# DA14580_QFN40_0v5_P.net
KiCad netlist of a schematic drawn in EAGLE
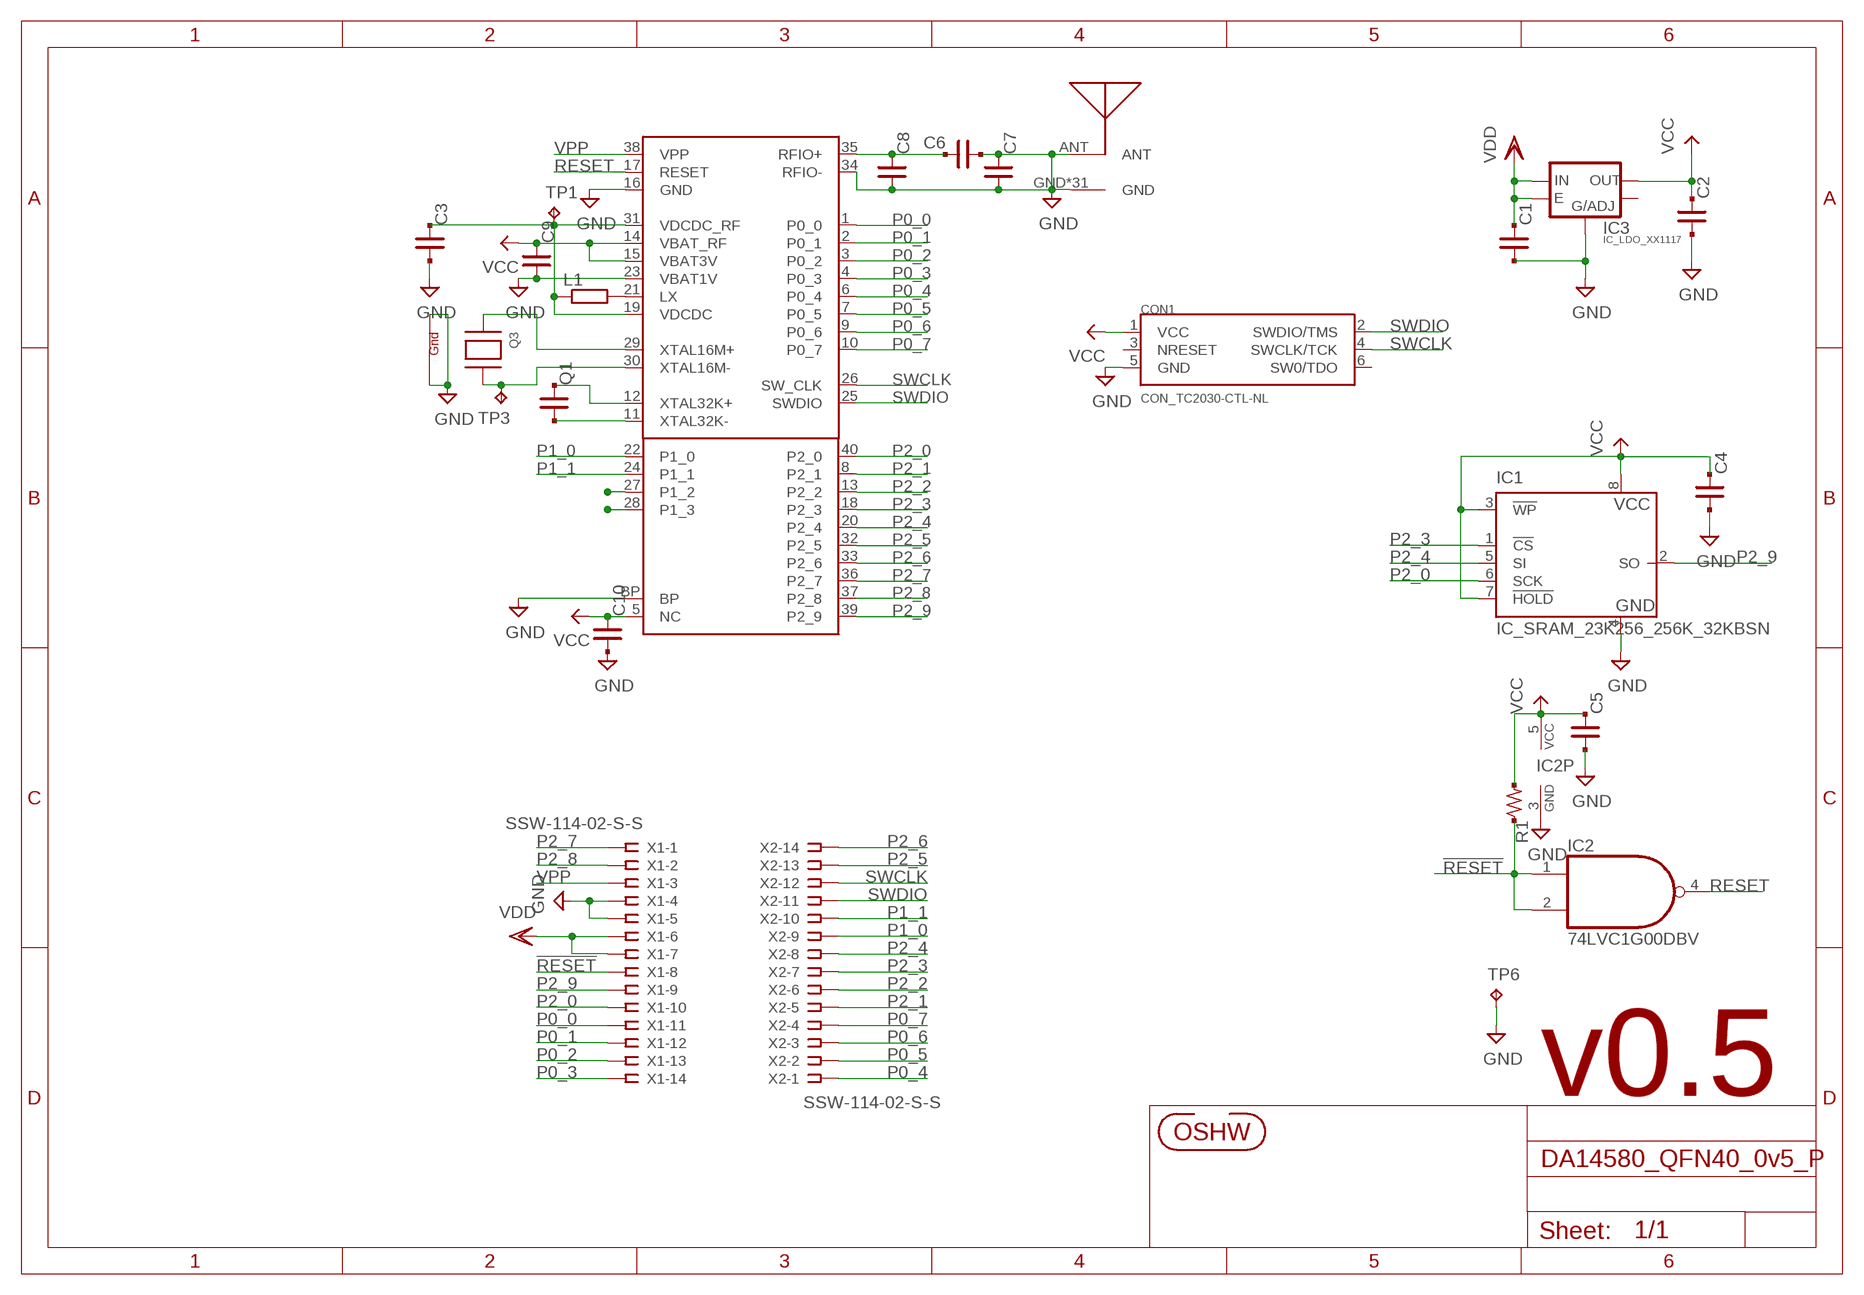
[diagram p0: schematic, sheet 1]

(export (version "E")
  (design (tool "Eeschema 10.0.6"))
  (components
    (comp (ref "C1")
      (value "C_PAD_PAD_1005")
      (footprint "eagle-import:C0402")
      (libsource (lib "eagle-import") (part "C_PAD_PAD_1005"))
    )
    (comp (ref "C2")
      (value "C_PAD_PAD_1005")
      (footprint "eagle-import:C0402")
      (libsource (lib "eagle-import") (part "C_PAD_PAD_1005"))
    )
    (comp (ref "C3")
      (value "C_PAD_PAD_1005")
      (footprint "eagle-import:C0402")
      (libsource (lib "eagle-import") (part "C_PAD_PAD_1005"))
    )
    (comp (ref "C4")
      (value "C_PAD_PAD_1005")
      (footprint "eagle-import:C0402")
      (libsource (lib "eagle-import") (part "C_PAD_PAD_1005"))
    )
    (comp (ref "C5")
      (value "C_PAD_PAD_1005")
      (footprint "eagle-import:C0402")
      (libsource (lib "eagle-import") (part "C_PAD_PAD_1005"))
    )
    (comp (ref "C6")
      (value "C_PAD_PAD_1005")
      (footprint "eagle-import:C0402")
      (libsource (lib "eagle-import") (part "C_PAD_PAD_1005"))
    )
    (comp (ref "C7")
      (value "C_PAD_PAD_1005")
      (footprint "eagle-import:C0402")
      (libsource (lib "eagle-import") (part "C_PAD_PAD_1005"))
    )
    (comp (ref "C8")
      (value "C_PAD_PAD_1005")
      (footprint "eagle-import:C0402")
      (libsource (lib "eagle-import") (part "C_PAD_PAD_1005"))
    )
    (comp (ref "C9")
      (value "C_PAD_PAD_1005")
      (footprint "eagle-import:C0402")
      (libsource (lib "eagle-import") (part "C_PAD_PAD_1005"))
    )
    (comp (ref "C10")
      (value "C_PAD_PAD_1005")
      (footprint "eagle-import:C0402")
      (libsource (lib "eagle-import") (part "C_PAD_PAD_1005"))
    )
    (comp (ref "CON1")
      (value "CON_TC2030-CTL-NL")
      (footprint "eagle-import:CON_TC2030-IDC-NL")
      (libsource (lib "eagle-import") (part "CON_TC2030-CTL-NL"))
    )
    (comp (ref "IC1")
      (value "IC_SRAM_23K256_256K_32KBSN")
      (footprint "eagle-import:IC_08_1.27_150MIL")
      (libsource (lib "eagle-import") (part "IC_SRAM_23K256_256K_32KBSN"))
    )
    (comp (ref "IC2")
      (value "74LVC1G00DBV")
      (footprint "eagle-import:SOT23-5")
      (libsource (lib "eagle-import") (part "741G00DBVLVC"))
    )
    (comp (ref "IC3")
      (value "IC_LDO_XX1117")
      (footprint "eagle-import:IC_05_0.95_50MIL")
      (libsource (lib "eagle-import") (part "IC_LDO_XX1117"))
    )
    (comp (ref "L1")
      (value "R-EU_R0603")
      (footprint "eagle-import:R0603")
      (libsource (lib "eagle-import") (part "R-EU_R0603"))
    )
    (comp (ref "Q1")
      (value "C_PAD_PAD_3216")
      (footprint "eagle-import:CR_3216")
      (libsource (lib "eagle-import") (part "C_PAD_PAD_3216"))
    )
    (comp (ref "Q3")
      (value "XTAL-4-3225")
      (footprint "eagle-import:NX3225")
      (libsource (lib "eagle-import") (part "XTAL-4-3225"))
    )
    (comp (ref "R1")
      (value "R_US_PAD_PAD_1005")
      (footprint "eagle-import:C0402")
      (libsource (lib "eagle-import") (part "R_US_PAD_PAD_1005"))
    )
    (comp (ref "TP1")
      (value "TPTP07R")
      (footprint "eagle-import:TP07R")
      (libsource (lib "eagle-import") (part "TPTP07R"))
    )
    (comp (ref "TP3")
      (value "TPTP07R")
      (footprint "eagle-import:TP07R")
      (libsource (lib "eagle-import") (part "TPTP07R"))
    )
    (comp (ref "TP6")
      (value "TPPAD1-13")
      (footprint "eagle-import:P1-13")
      (libsource (lib "eagle-import") (part "TPPAD1-13"))
    )
    (comp (ref "U$1")
      (value "ANT_IFA")
      (footprint "eagle-import:ANT_IFA_V2")
      (libsource (lib "eagle-import") (part "ANT_IFA"))
    )
    (comp (ref "U$2")
      (value "ICON_OSHW")
      (footprint "eagle-import:ICON_OSHW")
      (libsource (lib "eagle-import") (part "ICON_OSHW"))
    )
    (comp (ref "U1")
      (value "IC_DA14580_QFN40")
      (footprint "eagle-import:QFN40_0.4P5.0X5.0")
      (libsource (lib "eagle-import") (part "IC_DA14580_QFN40"))
    )
    (comp (ref "X1")
      (value "SSW-114-02-S-S")
      (footprint "eagle-import:SSW-114-02-S-S")
      (libsource (lib "eagle-import") (part "SSW-114-02-S-S"))
    )
    (comp (ref "X2")
      (value "SSW-114-02-S-S")
      (footprint "eagle-import:SSW-114-02-S-S")
      (libsource (lib "eagle-import") (part "SSW-114-02-S-S"))
    )
  )
  (nets
    (net (code "1") (name "/P0_0") (class "Default")
      (node (ref "U1") (pin "1") (pinfunction "P0_0_1") (pintype "bidirectional"))
      (node (ref "X1") (pin "11") (pinfunction "1_11") (pintype "passive"))
    )
    (net (code "2") (name "/P0_1") (class "Default")
      (node (ref "U1") (pin "2") (pinfunction "P0_1_2") (pintype "bidirectional"))
      (node (ref "X1") (pin "12") (pinfunction "1_12") (pintype "passive"))
    )
    (net (code "3") (name "/P0_2") (class "Default")
      (node (ref "U1") (pin "3") (pinfunction "P0_2_3") (pintype "bidirectional"))
      (node (ref "X1") (pin "13") (pinfunction "1_13") (pintype "passive"))
    )
    (net (code "4") (name "/P0_3") (class "Default")
      (node (ref "U1") (pin "4") (pinfunction "P0_3_4") (pintype "bidirectional"))
      (node (ref "X1") (pin "14") (pinfunction "1_14") (pintype "passive"))
    )
    (net (code "5") (name "/P0_4") (class "Default")
      (node (ref "U1") (pin "6") (pinfunction "P0_4_6") (pintype "bidirectional"))
      (node (ref "X2") (pin "1") (pinfunction "1_1") (pintype "passive"))
    )
    (net (code "6") (name "/P0_5") (class "Default")
      (node (ref "U1") (pin "7") (pinfunction "P0_5_7") (pintype "bidirectional"))
      (node (ref "X2") (pin "2") (pinfunction "1_2") (pintype "passive"))
    )
    (net (code "7") (name "/P0_6") (class "Default")
      (node (ref "U1") (pin "9") (pinfunction "P0_6_9") (pintype "bidirectional"))
      (node (ref "X2") (pin "3") (pinfunction "1_3") (pintype "passive"))
    )
    (net (code "8") (name "/P0_7") (class "Default")
      (node (ref "U1") (pin "10") (pinfunction "P0_7_10") (pintype "bidirectional"))
      (node (ref "X2") (pin "4") (pinfunction "1_4") (pintype "passive"))
    )
    (net (code "9") (name "/P1_0") (class "Default")
      (node (ref "U1") (pin "22") (pinfunction "P1_0_22") (pintype "bidirectional"))
      (node (ref "X2") (pin "9") (pinfunction "1_9") (pintype "passive"))
    )
    (net (code "10") (name "/P1_1") (class "Default")
      (node (ref "U1") (pin "24") (pinfunction "P1_1_24") (pintype "bidirectional"))
      (node (ref "X2") (pin "10") (pinfunction "1_10") (pintype "passive"))
    )
    (net (code "11") (name "/P2_0") (class "Default")
      (node (ref "IC1") (pin "6") (pinfunction "SCK_6") (pintype "input"))
      (node (ref "U1") (pin "40") (pinfunction "P2_0_40") (pintype "bidirectional"))
      (node (ref "X1") (pin "10") (pinfunction "1_10") (pintype "passive"))
    )
    (net (code "12") (name "/P2_1") (class "Default")
      (node (ref "U1") (pin "8") (pinfunction "P2_1_8") (pintype "bidirectional"))
      (node (ref "X2") (pin "5") (pinfunction "1_5") (pintype "passive"))
    )
    (net (code "13") (name "/P2_2") (class "Default")
      (node (ref "U1") (pin "13") (pinfunction "P2_2_13") (pintype "bidirectional"))
      (node (ref "X2") (pin "6") (pinfunction "1_6") (pintype "passive"))
    )
    (net (code "14") (name "/P2_3") (class "Default")
      (node (ref "IC1") (pin "1") (pinfunction "~{CS}_1") (pintype "input"))
      (node (ref "U1") (pin "18") (pinfunction "P2_3_18") (pintype "bidirectional"))
      (node (ref "X2") (pin "7") (pinfunction "1_7") (pintype "passive"))
    )
    (net (code "15") (name "/P2_4") (class "Default")
      (node (ref "IC1") (pin "5") (pinfunction "SI_5") (pintype "input"))
      (node (ref "U1") (pin "20") (pinfunction "P2_4_20") (pintype "bidirectional"))
      (node (ref "X2") (pin "8") (pinfunction "1_8") (pintype "passive"))
    )
    (net (code "16") (name "/P2_5") (class "Default")
      (node (ref "U1") (pin "32") (pinfunction "P2_5_32") (pintype "bidirectional"))
      (node (ref "X2") (pin "13") (pinfunction "1_13") (pintype "passive"))
    )
    (net (code "17") (name "/P2_6") (class "Default")
      (node (ref "U1") (pin "33") (pinfunction "P2_6_33") (pintype "bidirectional"))
      (node (ref "X2") (pin "14") (pinfunction "1_14") (pintype "passive"))
    )
    (net (code "18") (name "/P2_7") (class "Default")
      (node (ref "U1") (pin "36") (pinfunction "P2_7_36") (pintype "bidirectional"))
      (node (ref "X1") (pin "1") (pinfunction "1_1") (pintype "passive"))
    )
    (net (code "19") (name "/P2_8") (class "Default")
      (node (ref "U1") (pin "37") (pinfunction "P2_8_37") (pintype "bidirectional"))
      (node (ref "X1") (pin "2") (pinfunction "1_2") (pintype "passive"))
    )
    (net (code "20") (name "/P2_9") (class "Default")
      (node (ref "IC1") (pin "2") (pinfunction "SO_2") (pintype "bidirectional"))
      (node (ref "U1") (pin "39") (pinfunction "P2_9_39") (pintype "bidirectional"))
      (node (ref "X1") (pin "9") (pinfunction "1_9") (pintype "passive"))
    )
    (net (code "21") (name "/RESET") (class "Default")
      (node (ref "IC2") (pin "4") (pinfunction "O_4") (pintype "output"))
      (node (ref "U1") (pin "17") (pinfunction "RESET_17") (pintype "bidirectional"))
    )
    (net (code "22") (name "/SWCLK") (class "Default")
      (node (ref "CON1") (pin "4") (pinfunction "SWCLK/TCK_4") (pintype "bidirectional"))
      (node (ref "U1") (pin "26") (pinfunction "SW_CLK_26") (pintype "bidirectional"))
      (node (ref "X2") (pin "12") (pinfunction "1_12") (pintype "passive"))
    )
    (net (code "23") (name "/SWDIO") (class "Default")
      (node (ref "CON1") (pin "2") (pinfunction "SWDIO/TMS_2") (pintype "bidirectional"))
      (node (ref "U1") (pin "25") (pinfunction "SWDIO_25") (pintype "bidirectional"))
      (node (ref "X2") (pin "11") (pinfunction "1_11") (pintype "passive"))
    )
    (net (code "24") (name "/VPP") (class "Default")
      (node (ref "U1") (pin "38") (pinfunction "VPP_38") (pintype "bidirectional"))
      (node (ref "X1") (pin "3") (pinfunction "1_3") (pintype "passive"))
    )
    (net (code "25") (name "/~{RESET}") (class "Default")
      (node (ref "IC2") (pin "1") (pinfunction "I0_1") (pintype "input"))
      (node (ref "IC2") (pin "2") (pinfunction "I1_2") (pintype "input"))
      (node (ref "R1") (pin "1") (pinfunction "1_1") (pintype "passive"))
      (node (ref "X1") (pin "8") (pinfunction "1_8") (pintype "passive"))
    )
    (net (code "26") (name "GND") (class "Default")
      (node (ref "C1") (pin "2") (pinfunction "2_2") (pintype "passive"))
      (node (ref "C10") (pin "2") (pinfunction "2_2") (pintype "passive"))
      (node (ref "C2") (pin "2") (pinfunction "2_2") (pintype "passive"))
      (node (ref "C3") (pin "2") (pinfunction "2_2") (pintype "passive"))
      (node (ref "C4") (pin "2") (pinfunction "2_2") (pintype "passive"))
      (node (ref "C5") (pin "2") (pinfunction "2_2") (pintype "passive"))
      (node (ref "C6") (pin "2") (pinfunction "2_2") (pintype "passive"))
      (node (ref "C7") (pin "1") (pinfunction "1_1") (pintype "passive"))
      (node (ref "C7") (pin "2") (pinfunction "2_2") (pintype "passive"))
      (node (ref "C8") (pin "2") (pinfunction "2_2") (pintype "passive"))
      (node (ref "C9") (pin "2") (pinfunction "2_2") (pintype "passive"))
      (node (ref "CON1") (pin "5") (pinfunction "GND_5") (pintype "bidirectional"))
      (node (ref "IC1") (pin "4") (pinfunction "GND_4") (pintype "power_in"))
      (node (ref "IC2") (pin "3") (pinfunction "GND_3") (pintype "power_in"))
      (node (ref "IC3") (pin "2") (pinfunction "ADJ_2") (pintype "input"))
      (node (ref "Q3") (pin "2") (pinfunction "G2_2") (pintype "power_in"))
      (node (ref "Q3") (pin "4") (pinfunction "G1_4") (pintype "power_in"))
      (node (ref "TP6") (pin "TP") (pinfunction "TP_TP") (pintype "input"))
      (node (ref "U$1") (pin "ANT") (pinfunction "ANT_ANT") (pintype "bidirectional"))
      (node (ref "U$1") (pin "GND") (pinfunction "GND_GND") (pintype "bidirectional"))
      (node (ref "U$1") (pin "GND@1") (pinfunction "GND_GND@1") (pintype "bidirectional"))
      (node (ref "U$1") (pin "GND@10") (pinfunction "GND_GND@10") (pintype "bidirectional"))
      (node (ref "U$1") (pin "GND@11") (pinfunction "GND_GND@11") (pintype "bidirectional"))
      (node (ref "U$1") (pin "GND@12") (pinfunction "GND_GND@12") (pintype "bidirectional"))
      (node (ref "U$1") (pin "GND@13") (pinfunction "GND_GND@13") (pintype "bidirectional"))
      (node (ref "U$1") (pin "GND@14") (pinfunction "GND_GND@14") (pintype "bidirectional"))
      (node (ref "U$1") (pin "GND@15") (pinfunction "GND_GND@15") (pintype "bidirectional"))
      (node (ref "U$1") (pin "GND@16") (pinfunction "GND_GND@16") (pintype "bidirectional"))
      (node (ref "U$1") (pin "GND@17") (pinfunction "GND_GND@17") (pintype "bidirectional"))
      (node (ref "U$1") (pin "GND@18") (pinfunction "GND_GND@18") (pintype "bidirectional"))
      (node (ref "U$1") (pin "GND@19") (pinfunction "GND_GND@19") (pintype "bidirectional"))
      (node (ref "U$1") (pin "GND@2") (pinfunction "GND_GND@2") (pintype "bidirectional"))
      (node (ref "U$1") (pin "GND@20") (pinfunction "GND_GND@20") (pintype "bidirectional"))
      (node (ref "U$1") (pin "GND@21") (pinfunction "GND_GND@21") (pintype "bidirectional"))
      (node (ref "U$1") (pin "GND@22") (pinfunction "GND_GND@22") (pintype "bidirectional"))
      (node (ref "U$1") (pin "GND@23") (pinfunction "GND_GND@23") (pintype "bidirectional"))
      (node (ref "U$1") (pin "GND@24") (pinfunction "GND_GND@24") (pintype "bidirectional"))
      (node (ref "U$1") (pin "GND@25") (pinfunction "GND_GND@25") (pintype "bidirectional"))
      (node (ref "U$1") (pin "GND@26") (pinfunction "GND_GND@26") (pintype "bidirectional"))
      (node (ref "U$1") (pin "GND@27") (pinfunction "GND_GND@27") (pintype "bidirectional"))
      (node (ref "U$1") (pin "GND@28") (pinfunction "GND_GND@28") (pintype "bidirectional"))
      (node (ref "U$1") (pin "GND@29") (pinfunction "GND_GND@29") (pintype "bidirectional"))
      (node (ref "U$1") (pin "GND@3") (pinfunction "GND_GND@3") (pintype "bidirectional"))
      (node (ref "U$1") (pin "GND@30") (pinfunction "GND_GND@30") (pintype "bidirectional"))
      (node (ref "U$1") (pin "GND@4") (pinfunction "GND_GND@4") (pintype "bidirectional"))
      (node (ref "U$1") (pin "GND@5") (pinfunction "GND_GND@5") (pintype "bidirectional"))
      (node (ref "U$1") (pin "GND@6") (pinfunction "GND_GND@6") (pintype "bidirectional"))
      (node (ref "U$1") (pin "GND@7") (pinfunction "GND_GND@7") (pintype "bidirectional"))
      (node (ref "U$1") (pin "GND@8") (pinfunction "GND_GND@8") (pintype "bidirectional"))
      (node (ref "U$1") (pin "GND@9") (pinfunction "GND_GND@9") (pintype "bidirectional"))
      (node (ref "U1") (pin "16") (pinfunction "GND_16") (pintype "bidirectional"))
      (node (ref "U1") (pin "23") (pinfunction "VBAT1V_23") (pintype "bidirectional"))
      (node (ref "U1") (pin "34") (pinfunction "RFIO-_34") (pintype "bidirectional"))
      (node (ref "U1") (pin "BP") (pinfunction "BP_BP") (pintype "bidirectional"))
      (node (ref "X1") (pin "4") (pinfunction "1_4") (pintype "passive"))
      (node (ref "X1") (pin "5") (pinfunction "1_5") (pintype "passive"))
    )
    (net (code "27") (name "Net-(Q3-X1)") (class "Default")
      (node (ref "Q3") (pin "1") (pinfunction "X1_1") (pintype "bidirectional"))
      (node (ref "U1") (pin "29") (pinfunction "XTAL16M+_29") (pintype "bidirectional"))
    )
    (net (code "28") (name "Net-(Q3-X2)") (class "Default")
      (node (ref "Q3") (pin "3") (pinfunction "X2_3") (pintype "bidirectional"))
      (node (ref "TP3") (pin "TP") (pinfunction "TP_TP") (pintype "input"))
      (node (ref "U1") (pin "30") (pinfunction "XTAL16M-_30") (pintype "bidirectional"))
    )
    (net (code "29") (name "Net-(U1-LX)") (class "Default")
      (node (ref "L1") (pin "2") (pinfunction "2_2") (pintype "passive"))
      (node (ref "U1") (pin "21") (pinfunction "LX_21") (pintype "bidirectional"))
    )
    (net (code "30") (name "Net-(U1-RFIO+)") (class "Default")
      (node (ref "C6") (pin "1") (pinfunction "1_1") (pintype "passive"))
      (node (ref "C8") (pin "1") (pinfunction "1_1") (pintype "passive"))
      (node (ref "U1") (pin "35") (pinfunction "RFIO+_35") (pintype "bidirectional"))
    )
    (net (code "31") (name "Net-(U1-VDCDC)") (class "Default")
      (node (ref "C3") (pin "1") (pinfunction "1_1") (pintype "passive"))
      (node (ref "L1") (pin "1") (pinfunction "1_1") (pintype "passive"))
      (node (ref "TP1") (pin "TP") (pinfunction "TP_TP") (pintype "input"))
      (node (ref "U1") (pin "19") (pinfunction "VDCDC_19") (pintype "bidirectional"))
      (node (ref "U1") (pin "31") (pinfunction "VDCDC_RF_31") (pintype "bidirectional"))
    )
    (net (code "32") (name "Net-(U1-XTAL32K+)") (class "Default")
      (node (ref "Q1") (pin "1") (pinfunction "1_1") (pintype "passive"))
      (node (ref "U1") (pin "12") (pinfunction "XTAL32K+_12") (pintype "bidirectional"))
    )
    (net (code "33") (name "Net-(U1-XTAL32K-)") (class "Default")
      (node (ref "Q1") (pin "2") (pinfunction "2_2") (pintype "passive"))
      (node (ref "U1") (pin "11") (pinfunction "XTAL32K-_11") (pintype "bidirectional"))
    )
    (net (code "34") (name "VCC") (class "Default")
      (node (ref "C10") (pin "1") (pinfunction "1_1") (pintype "passive"))
      (node (ref "C2") (pin "1") (pinfunction "1_1") (pintype "passive"))
      (node (ref "C4") (pin "1") (pinfunction "1_1") (pintype "passive"))
      (node (ref "C5") (pin "1") (pinfunction "1_1") (pintype "passive"))
      (node (ref "C9") (pin "1") (pinfunction "1_1") (pintype "passive"))
      (node (ref "CON1") (pin "1") (pinfunction "VCC_1") (pintype "bidirectional"))
      (node (ref "IC1") (pin "3") (pinfunction "~{WP}_3") (pintype "input"))
      (node (ref "IC1") (pin "7") (pinfunction "~{HOLD}_7") (pintype "input"))
      (node (ref "IC1") (pin "8") (pinfunction "VCC_8") (pintype "power_in"))
      (node (ref "IC2") (pin "5") (pinfunction "VCC_5") (pintype "power_in"))
      (node (ref "IC3") (pin "5") (pinfunction "OUT_5") (pintype "output"))
      (node (ref "R1") (pin "2") (pinfunction "2_2") (pintype "passive"))
      (node (ref "U1") (pin "14") (pinfunction "VBAT_RF_14") (pintype "bidirectional"))
      (node (ref "U1") (pin "15") (pinfunction "VBAT3V_15") (pintype "bidirectional"))
      (node (ref "U1") (pin "5") (pinfunction "NC_5") (pintype "bidirectional"))
    )
    (net (code "35") (name "VDD") (class "Default")
      (node (ref "C1") (pin "1") (pinfunction "1_1") (pintype "passive"))
      (node (ref "IC3") (pin "1") (pinfunction "IN_1") (pintype "input"))
      (node (ref "IC3") (pin "3") (pinfunction "E_3") (pintype "input"))
      (node (ref "X1") (pin "6") (pinfunction "1_6") (pintype "passive"))
      (node (ref "X1") (pin "7") (pinfunction "1_7") (pintype "passive"))
    )
    (net (code "36") (name "unconnected-(CON1-NRESET-Pad3)") (class "Default")
      (node (ref "CON1") (pin "3") (pinfunction "NRESET_3") (pintype "bidirectional"))
    )
    (net (code "37") (name "unconnected-(CON1-SW0{slash}TDO-Pad6)") (class "Default")
      (node (ref "CON1") (pin "6") (pinfunction "SW0/TDO_6") (pintype "bidirectional"))
    )
    (net (code "38") (name "unconnected-(IC3-OUT-Pad4)") (class "Default")
      (node (ref "IC3") (pin "4") (pinfunction "OUT_4") (pintype "output"))
    )
    (net (code "39") (name "unconnected-(U1-P1_2-Pad27)") (class "Default")
      (node (ref "U1") (pin "27") (pinfunction "P1_2_27") (pintype "bidirectional"))
    )
    (net (code "40") (name "unconnected-(U1-P1_3-Pad28)") (class "Default")
      (node (ref "U1") (pin "28") (pinfunction "P1_3_28") (pintype "bidirectional"))
    )
  )
)
